# 555_Timer.net
KiCad netlist of a schematic drawn in EAGLE
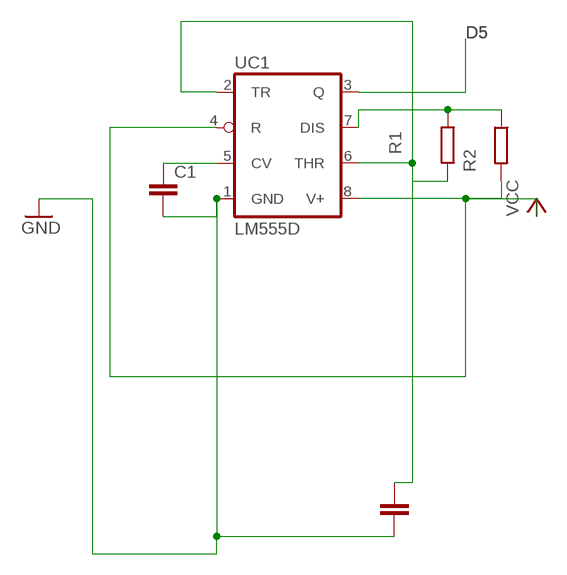
[diagram p0: schematic, sheet 1]

(export (version "E")
  (design (tool "Eeschema 10.0.6"))
  (components
    (comp (ref "C1")
      (value "C-EU025-024X044")
      (footprint "eagle-import:C025-024X044")
      (libsource (lib "eagle-import") (part "C-EU025-024X044"))
    )
    (comp (ref "C3")
      (value "C-EU025-024X044")
      (footprint "eagle-import:C025-024X044")
      (libsource (lib "eagle-import") (part "C-EU025-024X044"))
    )
    (comp (ref "R1")
      (value "R-EU_0204/5")
      (footprint "eagle-import:0204_5")
      (libsource (lib "eagle-import") (part "R-EU_0204/5"))
    )
    (comp (ref "R2")
      (value "R-EU_0204/5")
      (footprint "eagle-import:0204_5")
      (libsource (lib "eagle-import") (part "R-EU_0204/5"))
    )
    (comp (ref "UC1")
      (value "LM555D")
      (footprint "eagle-import:SO08")
      (libsource (lib "eagle-import") (part "555DLM"))
    )
  )
  (nets
    (net (code "1") (name "/D5") (class "Default")
      (node (ref "UC1") (pin "3") (pinfunction "Q_3") (pintype "output"))
    )
    (net (code "2") (name "GND") (class "Default")
      (node (ref "C1") (pin "2") (pinfunction "2_2") (pintype "passive"))
      (node (ref "C3") (pin "2") (pinfunction "2_2") (pintype "passive"))
      (node (ref "UC1") (pin "1") (pinfunction "GND_1") (pintype "power_in"))
    )
    (net (code "3") (name "Net-(UC1-CV)") (class "Default")
      (node (ref "C1") (pin "1") (pinfunction "1_1") (pintype "passive"))
      (node (ref "UC1") (pin "5") (pinfunction "CV_5") (pintype "input"))
    )
    (net (code "4") (name "Net-(UC1-DIS)") (class "Default")
      (node (ref "R1") (pin "2") (pinfunction "2_2") (pintype "passive"))
      (node (ref "R2") (pin "1") (pinfunction "1_1") (pintype "passive"))
      (node (ref "UC1") (pin "7") (pinfunction "DIS_7") (pintype "input"))
    )
    (net (code "5") (name "Net-(UC1-THR)") (class "Default")
      (node (ref "C3") (pin "1") (pinfunction "1_1") (pintype "passive"))
      (node (ref "R1") (pin "1") (pinfunction "1_1") (pintype "passive"))
      (node (ref "UC1") (pin "2") (pinfunction "TR_2") (pintype "input"))
      (node (ref "UC1") (pin "6") (pinfunction "THR_6") (pintype "input"))
    )
    (net (code "6") (name "VCC") (class "Default")
      (node (ref "R2") (pin "2") (pinfunction "2_2") (pintype "passive"))
      (node (ref "UC1") (pin "4") (pinfunction "R_4") (pintype "input"))
      (node (ref "UC1") (pin "8") (pinfunction "V+_8") (pintype "power_in"))
    )
  )
)
